# MCU.net
KiCad netlist of a schematic drawn in Altium Designer
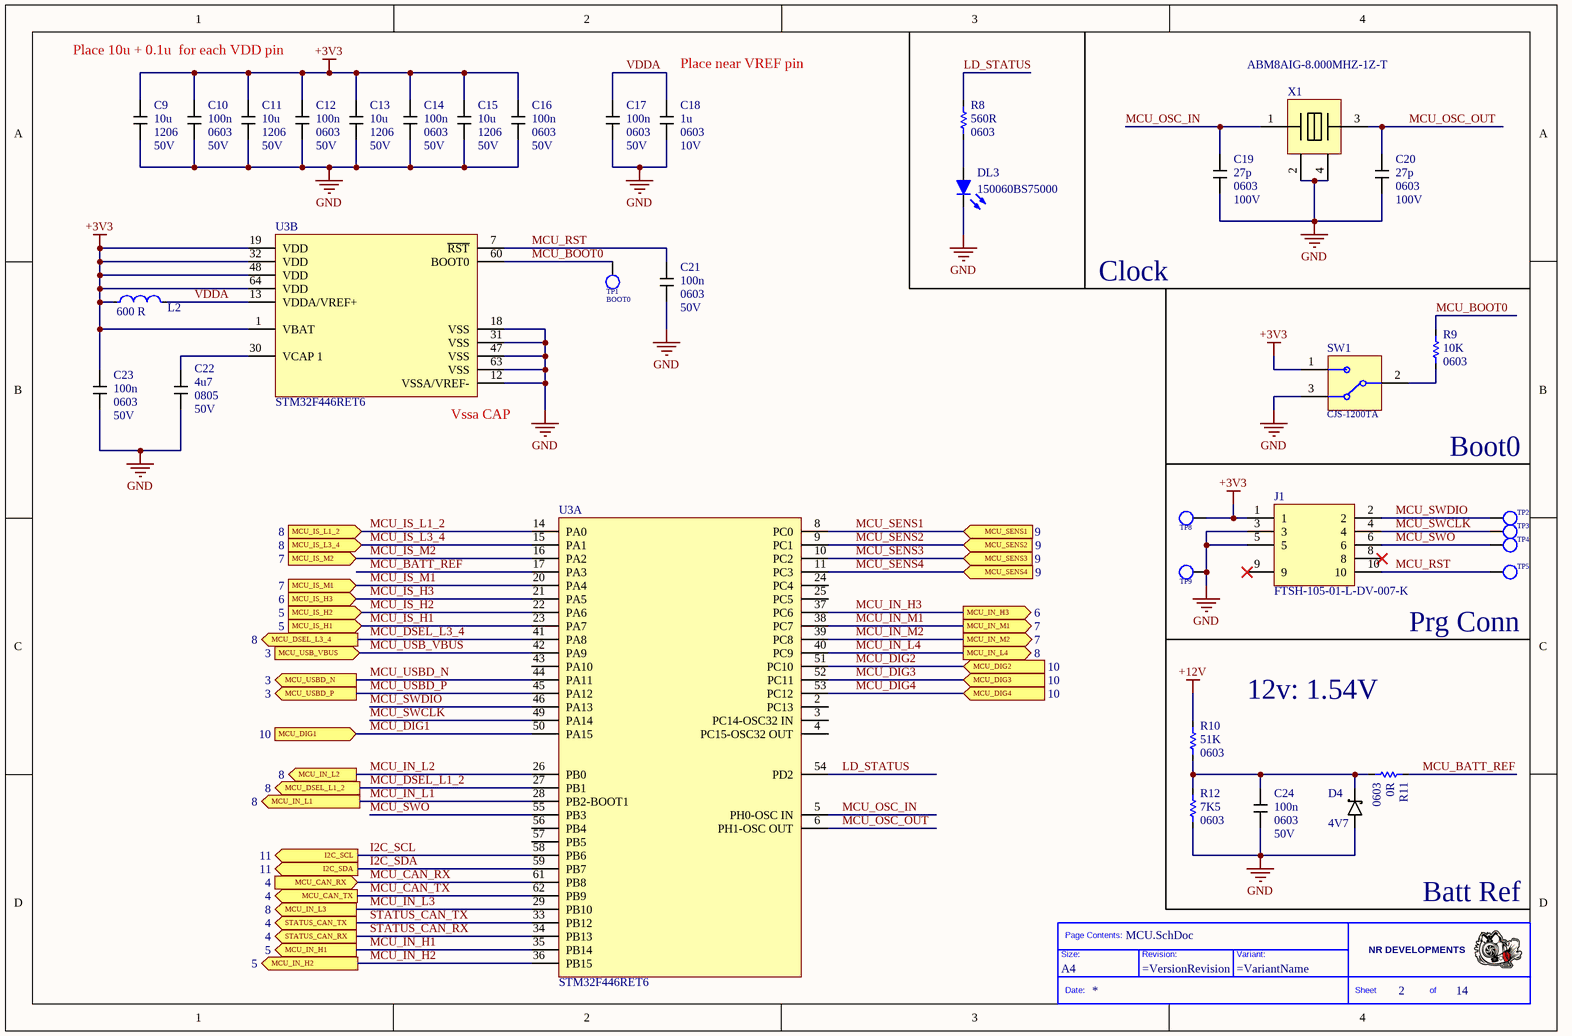
[diagram p0: MCU.SchDoc]

(export (version "E")
  (design (tool "Eeschema 10.0.6"))
  (components
    (comp (ref "C9")
      (value "10u")
      (footprint "CAPC3216X16M")
      (fields
        (field (name "CASE") "1206")
        (field (name "VOLTAGE") "50V")
        (field (name "MANUFACTURER") "Samsung Electro-Mechanics")
        (field (name "PARTNUMBER") "CL31B106KBHNNNE")
        (field (name "Comment") "CAP")
      )
      (libsource (lib "My_LIB") (part "CAP"))
    )
    (comp (ref "C10")
      (value "100n")
      (footprint "CAPC1608X09M")
      (fields
        (field (name "CASE") "0603")
        (field (name "VOLTAGE") "50V")
        (field (name "MANUFACTURER") "KEMET")
        (field (name "PARTNUMBER") "C0603C104K5RACTU")
        (field (name "Comment") "CAP")
      )
      (libsource (lib "My_LIB") (part "CAP"))
    )
    (comp (ref "C11")
      (value "10u")
      (footprint "CAPC3216X16M")
      (fields
        (field (name "CASE") "1206")
        (field (name "VOLTAGE") "50V")
        (field (name "MANUFACTURER") "Samsung Electro-Mechanics")
        (field (name "PARTNUMBER") "CL31B106KBHNNNE")
        (field (name "Comment") "CAP")
      )
      (libsource (lib "My_LIB") (part "CAP"))
    )
    (comp (ref "C12")
      (value "100n")
      (footprint "CAPC1608X09M")
      (fields
        (field (name "CASE") "0603")
        (field (name "VOLTAGE") "50V")
        (field (name "MANUFACTURER") "KEMET")
        (field (name "PARTNUMBER") "C0603C104K5RACTU")
        (field (name "Comment") "CAP")
      )
      (libsource (lib "My_LIB") (part "CAP"))
    )
    (comp (ref "C13")
      (value "10u")
      (footprint "CAPC3216X16M")
      (fields
        (field (name "CASE") "1206")
        (field (name "VOLTAGE") "50V")
        (field (name "MANUFACTURER") "Samsung Electro-Mechanics")
        (field (name "PARTNUMBER") "CL31B106KBHNNNE")
        (field (name "Comment") "CAP")
      )
      (libsource (lib "My_LIB") (part "CAP"))
    )
    (comp (ref "C14")
      (value "100n")
      (footprint "CAPC1608X09M")
      (fields
        (field (name "CASE") "0603")
        (field (name "VOLTAGE") "50V")
        (field (name "MANUFACTURER") "KEMET")
        (field (name "PARTNUMBER") "C0603C104K5RACTU")
        (field (name "Comment") "CAP")
      )
      (libsource (lib "My_LIB") (part "CAP"))
    )
    (comp (ref "C15")
      (value "10u")
      (footprint "CAPC3216X16M")
      (fields
        (field (name "CASE") "1206")
        (field (name "VOLTAGE") "50V")
        (field (name "MANUFACTURER") "Samsung Electro-Mechanics")
        (field (name "PARTNUMBER") "CL31B106KBHNNNE")
        (field (name "Comment") "CAP")
      )
      (libsource (lib "My_LIB") (part "CAP"))
    )
    (comp (ref "C16")
      (value "100n")
      (footprint "CAPC1608X09M")
      (fields
        (field (name "CASE") "0603")
        (field (name "VOLTAGE") "50V")
        (field (name "MANUFACTURER") "KEMET")
        (field (name "PARTNUMBER") "C0603C104K5RACTU")
        (field (name "Comment") "CAP")
      )
      (libsource (lib "My_LIB") (part "CAP"))
    )
    (comp (ref "C17")
      (value "100n")
      (footprint "CAPC1608X09M")
      (fields
        (field (name "CASE") "0603")
        (field (name "VOLTAGE") "50V")
        (field (name "MANUFACTURER") "KEMET")
        (field (name "PARTNUMBER") "C0603C104K5RACTU")
        (field (name "Comment") "CAP")
      )
      (libsource (lib "My_LIB") (part "CAP"))
    )
    (comp (ref "C18")
      (value "1u")
      (footprint "CAPC1608X09M")
      (fields
        (field (name "CASE") "0603")
        (field (name "VOLTAGE") "10V")
        (field (name "MANUFACTURER") "KEMET")
        (field (name "PARTNUMBER") "C0603C105K8RACTU")
        (field (name "Comment") "CAP")
      )
      (libsource (lib "My_LIB") (part "CAP"))
    )
    (comp (ref "C19")
      (value "27p")
      (footprint "CAPC1608X09M")
      (fields
        (field (name "CASE") "0603")
        (field (name "VOLTAGE") "100V")
        (field (name "MANUFACTURER") "YAGEO")
        (field (name "PARTNUMBER") "CC0603FRNPO0BN270")
        (field (name "Comment") "CAP")
      )
      (libsource (lib "My_LIB") (part "CAP"))
    )
    (comp (ref "C20")
      (value "27p")
      (footprint "CAPC1608X09M")
      (fields
        (field (name "CASE") "0603")
        (field (name "VOLTAGE") "100V")
        (field (name "MANUFACTURER") "YAGEO")
        (field (name "PARTNUMBER") "CC0603FRNPO0BN270")
        (field (name "Comment") "CAP")
      )
      (libsource (lib "My_LIB") (part "CAP"))
    )
    (comp (ref "C21")
      (value "100n")
      (footprint "CAPC1608X09M")
      (fields
        (field (name "CASE") "0603")
        (field (name "VOLTAGE") "50V")
        (field (name "MANUFACTURER") "KEMET")
        (field (name "PARTNUMBER") "C0603C104K5RACTU")
        (field (name "Comment") "CAP")
      )
      (libsource (lib "My_LIB") (part "CAP"))
    )
    (comp (ref "C22")
      (value "4u7")
      (footprint "CAPC2012X14N")
      (fields
        (field (name "CASE") "0805")
        (field (name "VOLTAGE") "50V")
        (field (name "MANUFACTURER") "KEMET")
        (field (name "PARTNUMBER") "C1206C475K5RACTU")
        (field (name "Comment") "CAP")
      )
      (libsource (lib "My_LIB") (part "CAP"))
    )
    (comp (ref "C23")
      (value "100n")
      (footprint "CAPC1608X09M")
      (fields
        (field (name "CASE") "0603")
        (field (name "VOLTAGE") "50V")
        (field (name "MANUFACTURER") "KEMET")
        (field (name "PARTNUMBER") "C0603C104K5RACTU")
        (field (name "Comment") "CAP")
      )
      (libsource (lib "My_LIB") (part "CAP"))
    )
    (comp (ref "C24")
      (value "100n")
      (footprint "CAPC1608X09M")
      (fields
        (field (name "CASE") "0603")
        (field (name "VOLTAGE") "50V")
        (field (name "MANUFACTURER") "KEMET")
        (field (name "PARTNUMBER") "C0603C104K5RACTU")
        (field (name "Comment") "CAP")
      )
      (libsource (lib "My_LIB") (part "CAP"))
    )
    (comp (ref "D4")
      (value "4V7")
      (footprint "SOT65P210X100-3N - AC")
      (fields
        (field (name "MANUFACTURER") "Nexperia")
        (field (name "PARTNUMBER") "BZX84W-C4V7-QX")
        (field (name "Comment") "Diode_Schottky")
      )
      (libsource (lib "My_LIB") (part "Diode_Schottky"))
    )
    (comp (ref "DL3")
      (value "150060BS75000")
      (footprint "LED0603")
      (fields (field (name "MANUFACTURER") "Wurth Elektronik") (field (name "Comment") "Led_Green"))
      (libsource (lib "My_LIB") (part "LED_Blue"))
    )
    (comp (ref "J1")
      (value "FTSH-105-01-L-DV-007-K")
      (footprint "SAMTEC_FTSH-105-X-X-DV-007-P-X")
      (fields (field (name "MANUFACTURER") "Samtech") (field (name "Comment") "Connector"))
      (libsource (lib "My_LIB") (part "FTSH-105-X-X-DV-007-P-X"))
    )
    (comp (ref "L2")
      (value "600 R")
      (footprint "INDC1608X09N")
      (fields
        (field (name "MANUFACTURER") "TDK")
        (field (name "PARTNUMBER") "MMZ1608R601ATD25")
        (field (name "Comment") "IND")
      )
      (libsource (lib "My_LIB") (part "IND"))
    )
    (comp (ref "R8")
      (value "560R")
      (footprint "RESC1608X06M")
      (fields
        (field (name "CASE") "0603")
        (field (name "MANUFACTURER") "Vishay")
        (field (name "PARTNUMBER") "RC0603FR-07560RL")
        (field (name "Comment") "Res")
      )
      (libsource (lib "My_LIB") (part "Resistor"))
    )
    (comp (ref "R9")
      (value "10K")
      (footprint "RESC1608X06M")
      (fields
        (field (name "CASE") "0603")
        (field (name "MANUFACTURER") "YAGEO")
        (field (name "PARTNUMBER") "AC0603FR-0710KL")
        (field (name "Comment") "Res")
      )
      (libsource (lib "My_LIB") (part "Resistor"))
    )
    (comp (ref "R10")
      (value "51K")
      (footprint "RESC1608X06M")
      (fields
        (field (name "CASE") "0603")
        (field (name "MANUFACTURER") "Vishay")
        (field (name "PARTNUMBER") "CRCW060351K0FKEA")
        (field (name "Comment") "Res")
      )
      (libsource (lib "My_LIB") (part "Resistor"))
    )
    (comp (ref "R11")
      (value "0R")
      (footprint "RESC1608X06M")
      (fields
        (field (name "CASE") "0603")
        (field (name "MANUFACTURER") "YAGEO")
        (field (name "PARTNUMBER") "RC0603JR-070RL")
        (field (name "Comment") "Res")
      )
      (libsource (lib "My_LIB") (part "Resistor"))
    )
    (comp (ref "R12")
      (value "7K5")
      (footprint "RESC1608X06M")
      (fields
        (field (name "CASE") "0603")
        (field (name "MANUFACTURER") "Vishay")
        (field (name "PARTNUMBER") "CRCW06037K50FKEA")
        (field (name "Comment") "Res")
      )
      (libsource (lib "My_LIB") (part "Resistor"))
    )
    (comp (ref "SW1")
      (value "CJS-1200TA")
      (footprint "SW_CJS-1200TA")
      (fields (field (name "MANUFACTURER") "Nidec Components") (field (name "Comment") "Switch SPDT"))
      (libsource (lib "My_LIB") (part "SWITCH_SPDT"))
    )
    (comp (ref "TP1") (value "BOOT0") (footprint "TP_c200") (libsource (lib "My_LIB") (part "Test_Point")))
    (comp (ref "TP2") (value "DIO") (footprint "TP_c200") (libsource (lib "My_LIB") (part "Test_Point")))
    (comp (ref "TP3") (value "CLK") (footprint "TP_c200") (libsource (lib "My_LIB") (part "Test_Point")))
    (comp (ref "TP4") (value "SWO") (footprint "TP_c200") (libsource (lib "My_LIB") (part "Test_Point")))
    (comp (ref "TP5") (value "RST") (footprint "TP_c200") (libsource (lib "My_LIB") (part "Test_Point")))
    (comp (ref "TP8") (value "3V3") (footprint "TP_c200") (libsource (lib "My_LIB") (part "Test_Point")))
    (comp (ref "TP9") (value "GND") (footprint "TP_c200") (libsource (lib "My_LIB") (part "Test_Point")))
    (comp (ref "U3")
      (value "STM32F446RET6")
      (footprint "STM-LQFP64_M")
      (description "IC MCU 32BIT 512KB FLASH 64LQFP")
      (fields (field (name "MANUFACTURER") "ST"))
      (libsource (lib "My_LIB") (part "STM32F446RET6"))
    )
    (comp (ref "X1")
      (value "ABM8AIG-8.000MHZ-1Z-T")
      (footprint "ABM8G_abracon")
      (fields (field (name "MANUFACTURER") "Abracom"))
      (libsource (lib "My_LIB") (part "Crystal"))
    )
  )
  (nets
    (net (code "1") (name "+3V3") (class "Default")
      (node (ref "C10") (pin "1") (pinfunction "1_1") (pintype "passive"))
      (node (ref "C11") (pin "1") (pinfunction "1_1") (pintype "passive"))
      (node (ref "C12") (pin "1") (pinfunction "1_1") (pintype "passive"))
      (node (ref "C13") (pin "1") (pinfunction "1_1") (pintype "passive"))
      (node (ref "C14") (pin "1") (pinfunction "1_1") (pintype "passive"))
      (node (ref "C15") (pin "1") (pinfunction "1_1") (pintype "passive"))
      (node (ref "C16") (pin "1") (pinfunction "1_1") (pintype "passive"))
      (node (ref "C23") (pin "1") (pinfunction "1_1") (pintype "passive"))
      (node (ref "C9") (pin "1") (pinfunction "1_1") (pintype "passive"))
      (node (ref "J1") (pin "1") (pinfunction "1_1") (pintype "passive"))
      (node (ref "L2") (pin "1") (pinfunction "1_1") (pintype "passive"))
      (node (ref "SW1") (pin "1") (pinfunction "1_1") (pintype "passive"))
      (node (ref "TP8") (pin "1") (pinfunction "1_1") (pintype "passive"))
      (node (ref "U3") (pin "1") (pinfunction "VBAT_1") (pintype "power_in"))
      (node (ref "U3") (pin "19") (pinfunction "VDD_19") (pintype "power_in"))
      (node (ref "U3") (pin "32") (pinfunction "VDD_32") (pintype "power_in"))
      (node (ref "U3") (pin "48") (pinfunction "VDD_48") (pintype "power_in"))
      (node (ref "U3") (pin "64") (pinfunction "VDD_64") (pintype "power_in"))
    )
    (net (code "2") (name "+12V") (class "Default")
      (node (ref "R10") (pin "2") (pinfunction "2_2") (pintype "passive"))
    )
    (net (code "3") (name "/I2C_SCL") (class "Default")
      (node (ref "U3") (pin "58") (pinfunction "PB6_58") (pintype "passive"))
    )
    (net (code "4") (name "/I2C_SDA") (class "Default")
      (node (ref "U3") (pin "59") (pinfunction "PB7_59") (pintype "passive"))
    )
    (net (code "5") (name "/LD_STATUS") (class "Default")
      (node (ref "R8") (pin "2") (pinfunction "2_2") (pintype "passive"))
      (node (ref "U3") (pin "54") (pinfunction "PD2_54") (pintype "passive"))
    )
    (net (code "6") (name "/MCU_BATT_REF") (class "Default")
      (node (ref "R11") (pin "2") (pinfunction "2_2") (pintype "passive"))
      (node (ref "U3") (pin "17") (pinfunction "PA3_17") (pintype "passive"))
    )
    (net (code "7") (name "/MCU_BOOT0") (class "Default")
      (node (ref "R9") (pin "2") (pinfunction "2_2") (pintype "passive"))
      (node (ref "TP1") (pin "1") (pinfunction "1_1") (pintype "passive"))
      (node (ref "U3") (pin "60") (pinfunction "BOOT0_60") (pintype "passive"))
    )
    (net (code "8") (name "/MCU_CAN_RX") (class "Default")
      (node (ref "U3") (pin "61") (pinfunction "PB8_61") (pintype "passive"))
    )
    (net (code "9") (name "/MCU_CAN_TX") (class "Default")
      (node (ref "U3") (pin "62") (pinfunction "PB9_62") (pintype "passive"))
    )
    (net (code "10") (name "/MCU_DIG1") (class "Default")
      (node (ref "U3") (pin "50") (pinfunction "PA15_50") (pintype "passive"))
    )
    (net (code "11") (name "/MCU_DIG2") (class "Default")
      (node (ref "U3") (pin "51") (pinfunction "PC10_51") (pintype "passive"))
    )
    (net (code "12") (name "/MCU_DIG3") (class "Default")
      (node (ref "U3") (pin "52") (pinfunction "PC11_52") (pintype "passive"))
    )
    (net (code "13") (name "/MCU_DIG4") (class "Default")
      (node (ref "U3") (pin "53") (pinfunction "PC12_53") (pintype "passive"))
    )
    (net (code "14") (name "/MCU_DSEL_L1_2") (class "Default")
      (node (ref "U3") (pin "27") (pinfunction "PB1_27") (pintype "passive"))
    )
    (net (code "15") (name "/MCU_DSEL_L3_4") (class "Default")
      (node (ref "U3") (pin "41") (pinfunction "PA8_41") (pintype "passive"))
    )
    (net (code "16") (name "/MCU_IN_H1") (class "Default")
      (node (ref "U3") (pin "35") (pinfunction "PB14_35") (pintype "passive"))
    )
    (net (code "17") (name "/MCU_IN_H2") (class "Default")
      (node (ref "U3") (pin "36") (pinfunction "PB15_36") (pintype "passive"))
    )
    (net (code "18") (name "/MCU_IN_H3") (class "Default")
      (node (ref "U3") (pin "37") (pinfunction "PC6_37") (pintype "passive"))
    )
    (net (code "19") (name "/MCU_IN_L1") (class "Default")
      (node (ref "U3") (pin "28") (pinfunction "PB2-BOOT1_28") (pintype "passive"))
    )
    (net (code "20") (name "/MCU_IN_L2") (class "Default")
      (node (ref "U3") (pin "26") (pinfunction "PB0_26") (pintype "passive"))
    )
    (net (code "21") (name "/MCU_IN_L3") (class "Default")
      (node (ref "U3") (pin "29") (pinfunction "PB10_29") (pintype "passive"))
    )
    (net (code "22") (name "/MCU_IN_L4") (class "Default")
      (node (ref "U3") (pin "40") (pinfunction "PC9_40") (pintype "passive"))
    )
    (net (code "23") (name "/MCU_IN_M1") (class "Default")
      (node (ref "U3") (pin "38") (pinfunction "PC7_38") (pintype "passive"))
    )
    (net (code "24") (name "/MCU_IN_M2") (class "Default")
      (node (ref "U3") (pin "39") (pinfunction "PC8_39") (pintype "passive"))
    )
    (net (code "25") (name "/MCU_IS_H1") (class "Default")
      (node (ref "U3") (pin "23") (pinfunction "PA7_23") (pintype "passive"))
    )
    (net (code "26") (name "/MCU_IS_H2") (class "Default")
      (node (ref "U3") (pin "22") (pinfunction "PA6_22") (pintype "passive"))
    )
    (net (code "27") (name "/MCU_IS_H3") (class "Default")
      (node (ref "U3") (pin "21") (pinfunction "PA5_21") (pintype "passive"))
    )
    (net (code "28") (name "/MCU_IS_L1_2") (class "Default")
      (node (ref "U3") (pin "14") (pinfunction "PA0_14") (pintype "passive"))
    )
    (net (code "29") (name "/MCU_IS_L3_4") (class "Default")
      (node (ref "U3") (pin "15") (pinfunction "PA1_15") (pintype "passive"))
    )
    (net (code "30") (name "/MCU_IS_M1") (class "Default")
      (node (ref "U3") (pin "20") (pinfunction "PA4_20") (pintype "passive"))
    )
    (net (code "31") (name "/MCU_IS_M2") (class "Default")
      (node (ref "U3") (pin "16") (pinfunction "PA2_16") (pintype "passive"))
    )
    (net (code "32") (name "/MCU_OSC_IN") (class "Default")
      (node (ref "C19") (pin "1") (pinfunction "1_1") (pintype "passive"))
      (node (ref "U3") (pin "5") (pinfunction "PH0-OSC_IN_5") (pintype "passive"))
      (node (ref "X1") (pin "1") (pinfunction "1_1") (pintype "passive"))
    )
    (net (code "33") (name "/MCU_OSC_OUT") (class "Default")
      (node (ref "C20") (pin "1") (pinfunction "1_1") (pintype "passive"))
      (node (ref "U3") (pin "6") (pinfunction "PH1-OSC_OUT_6") (pintype "passive"))
      (node (ref "X1") (pin "3") (pinfunction "3_3") (pintype "passive"))
    )
    (net (code "34") (name "/MCU_RST") (class "Default")
      (node (ref "C21") (pin "1") (pinfunction "1_1") (pintype "passive"))
      (node (ref "J1") (pin "10") (pinfunction "10_10") (pintype "passive"))
      (node (ref "TP5") (pin "1") (pinfunction "1_1") (pintype "passive"))
      (node (ref "U3") (pin "7") (pinfunction "~{RST}_7") (pintype "passive"))
    )
    (net (code "35") (name "/MCU_SENS1") (class "Default")
      (node (ref "U3") (pin "8") (pinfunction "PC0_8") (pintype "passive"))
    )
    (net (code "36") (name "/MCU_SENS2") (class "Default")
      (node (ref "U3") (pin "9") (pinfunction "PC1_9") (pintype "passive"))
    )
    (net (code "37") (name "/MCU_SENS3") (class "Default")
      (node (ref "U3") (pin "10") (pinfunction "PC2_10") (pintype "passive"))
    )
    (net (code "38") (name "/MCU_SENS4") (class "Default")
      (node (ref "U3") (pin "11") (pinfunction "PC3_11") (pintype "passive"))
    )
    (net (code "39") (name "/MCU_SWCLK") (class "Default")
      (node (ref "J1") (pin "4") (pinfunction "4_4") (pintype "passive"))
      (node (ref "TP3") (pin "1") (pinfunction "1_1") (pintype "passive"))
      (node (ref "U3") (pin "49") (pinfunction "PA14_49") (pintype "passive"))
    )
    (net (code "40") (name "/MCU_SWDIO") (class "Default")
      (node (ref "J1") (pin "2") (pinfunction "2_2") (pintype "passive"))
      (node (ref "TP2") (pin "1") (pinfunction "1_1") (pintype "passive"))
      (node (ref "U3") (pin "46") (pinfunction "PA13_46") (pintype "passive"))
    )
    (net (code "41") (name "/MCU_SWO") (class "Default")
      (node (ref "J1") (pin "6") (pinfunction "6_6") (pintype "passive"))
      (node (ref "TP4") (pin "1") (pinfunction "1_1") (pintype "passive"))
      (node (ref "U3") (pin "55") (pinfunction "PB3_55") (pintype "passive"))
    )
    (net (code "42") (name "/MCU_USBD_N") (class "Default")
      (node (ref "U3") (pin "44") (pinfunction "PA11_44") (pintype "passive"))
    )
    (net (code "43") (name "/MCU_USBD_P") (class "Default")
      (node (ref "U3") (pin "45") (pinfunction "PA12_45") (pintype "passive"))
    )
    (net (code "44") (name "/MCU_USB_VBUS") (class "Default")
      (node (ref "U3") (pin "42") (pinfunction "PA9_42") (pintype "passive"))
    )
    (net (code "45") (name "/STATUS_CAN_RX") (class "Default")
      (node (ref "U3") (pin "34") (pinfunction "PB13_34") (pintype "passive"))
    )
    (net (code "46") (name "/STATUS_CAN_TX") (class "Default")
      (node (ref "U3") (pin "33") (pinfunction "PB12_33") (pintype "passive"))
    )
    (net (code "47") (name "/VDDA") (class "Default")
      (node (ref "C17") (pin "1") (pinfunction "1_1") (pintype "passive"))
      (node (ref "C18") (pin "1") (pinfunction "1_1") (pintype "passive"))
      (node (ref "L2") (pin "2") (pinfunction "2_2") (pintype "passive"))
      (node (ref "U3") (pin "13") (pinfunction "VDDA/VREF+_13") (pintype "power_in"))
    )
    (net (code "48") (name "GND") (class "Default")
      (node (ref "C10") (pin "2") (pinfunction "2_2") (pintype "passive"))
      (node (ref "C11") (pin "2") (pinfunction "2_2") (pintype "passive"))
      (node (ref "C12") (pin "2") (pinfunction "2_2") (pintype "passive"))
      (node (ref "C13") (pin "2") (pinfunction "2_2") (pintype "passive"))
      (node (ref "C14") (pin "2") (pinfunction "2_2") (pintype "passive"))
      (node (ref "C15") (pin "2") (pinfunction "2_2") (pintype "passive"))
      (node (ref "C16") (pin "2") (pinfunction "2_2") (pintype "passive"))
      (node (ref "C17") (pin "2") (pinfunction "2_2") (pintype "passive"))
      (node (ref "C18") (pin "2") (pinfunction "2_2") (pintype "passive"))
      (node (ref "C19") (pin "2") (pinfunction "2_2") (pintype "passive"))
      (node (ref "C20") (pin "2") (pinfunction "2_2") (pintype "passive"))
      (node (ref "C21") (pin "2") (pinfunction "2_2") (pintype "passive"))
      (node (ref "C22") (pin "2") (pinfunction "2_2") (pintype "passive"))
      (node (ref "C23") (pin "2") (pinfunction "2_2") (pintype "passive"))
      (node (ref "C24") (pin "2") (pinfunction "2_2") (pintype "passive"))
      (node (ref "C9") (pin "2") (pinfunction "2_2") (pintype "passive"))
      (node (ref "D4") (pin "A") (pinfunction "A_A") (pintype "passive"))
      (node (ref "DL3") (pin "C") (pinfunction "C_C") (pintype "passive"))
      (node (ref "J1") (pin "3") (pinfunction "3_3") (pintype "passive"))
      (node (ref "J1") (pin "5") (pinfunction "5_5") (pintype "passive"))
      (node (ref "R12") (pin "1") (pinfunction "1_1") (pintype "passive"))
      (node (ref "SW1") (pin "3") (pinfunction "3_3") (pintype "passive"))
      (node (ref "TP9") (pin "1") (pinfunction "1_1") (pintype "passive"))
      (node (ref "U3") (pin "12") (pinfunction "VSSA/VREF-_12") (pintype "power_in"))
      (node (ref "U3") (pin "18") (pinfunction "VSS_18") (pintype "power_in"))
      (node (ref "U3") (pin "31") (pinfunction "VSS_31") (pintype "power_in"))
      (node (ref "U3") (pin "47") (pinfunction "VSS_47") (pintype "power_in"))
      (node (ref "U3") (pin "63") (pinfunction "VSS_63") (pintype "power_in"))
      (node (ref "X1") (pin "2") (pinfunction "2_2") (pintype "passive"))
      (node (ref "X1") (pin "4") (pinfunction "4_4") (pintype "passive"))
    )
    (net (code "49") (name "Net-(C24-Pad1)") (class "Default")
      (node (ref "C24") (pin "1") (pinfunction "1_1") (pintype "passive"))
      (node (ref "D4") (pin "C") (pinfunction "C_C") (pintype "passive"))
      (node (ref "R10") (pin "1") (pinfunction "1_1") (pintype "passive"))
      (node (ref "R11") (pin "1") (pinfunction "1_1") (pintype "passive"))
      (node (ref "R12") (pin "2") (pinfunction "2_2") (pintype "passive"))
    )
    (net (code "50") (name "Net-(DL3-PadA)") (class "Default")
      (node (ref "DL3") (pin "A") (pinfunction "A_A") (pintype "passive"))
      (node (ref "R8") (pin "1") (pinfunction "1_1") (pintype "passive"))
    )
    (net (code "51") (name "Net-(R9-Pad1)") (class "Default")
      (node (ref "R9") (pin "1") (pinfunction "1_1") (pintype "passive"))
      (node (ref "SW1") (pin "2") (pinfunction "2_2") (pintype "passive"))
    )
    (net (code "52") (name "Net-(U3B-VCAP_1)") (class "Default")
      (node (ref "C22") (pin "1") (pinfunction "1_1") (pintype "passive"))
      (node (ref "U3") (pin "30") (pinfunction "VCAP_1_30") (pintype "power_in"))
    )
    (net (code "53") (name "unconnected-(J1-Pad8)") (class "Default")
      (node (ref "J1") (pin "8") (pinfunction "8_8") (pintype "passive+no_connect"))
    )
    (net (code "54") (name "unconnected-(J1-Pad9)") (class "Default")
      (node (ref "J1") (pin "9") (pinfunction "9_9") (pintype "passive+no_connect"))
    )
    (net (code "55") (name "unconnected-(U3A-PA10-Pad43)") (class "Default")
      (node (ref "U3") (pin "43") (pinfunction "PA10_43") (pintype "passive"))
    )
    (net (code "56") (name "unconnected-(U3A-PB4-Pad56)") (class "Default")
      (node (ref "U3") (pin "56") (pinfunction "PB4_56") (pintype "passive"))
    )
    (net (code "57") (name "unconnected-(U3A-PB5-Pad57)") (class "Default")
      (node (ref "U3") (pin "57") (pinfunction "PB5_57") (pintype "passive"))
    )
    (net (code "58") (name "unconnected-(U3A-PC4-Pad24)") (class "Default")
      (node (ref "U3") (pin "24") (pinfunction "PC4_24") (pintype "passive"))
    )
    (net (code "59") (name "unconnected-(U3A-PC5-Pad25)") (class "Default")
      (node (ref "U3") (pin "25") (pinfunction "PC5_25") (pintype "passive"))
    )
    (net (code "60") (name "unconnected-(U3A-PC13-Pad2)") (class "Default")
      (node (ref "U3") (pin "2") (pinfunction "PC13_2") (pintype "passive"))
    )
    (net (code "61") (name "unconnected-(U3A-PC14-OSC32_IN-Pad3)") (class "Default")
      (node (ref "U3") (pin "3") (pinfunction "PC14-OSC32_IN_3") (pintype "passive"))
    )
    (net (code "62") (name "unconnected-(U3A-PC15-OSC32_OUT-Pad4)") (class "Default")
      (node (ref "U3") (pin "4") (pinfunction "PC15-OSC32_OUT_4") (pintype "passive"))
    )
  )
)
